# Brd_schematic.net
KiCad netlist of a schematic drawn in Altium Designer
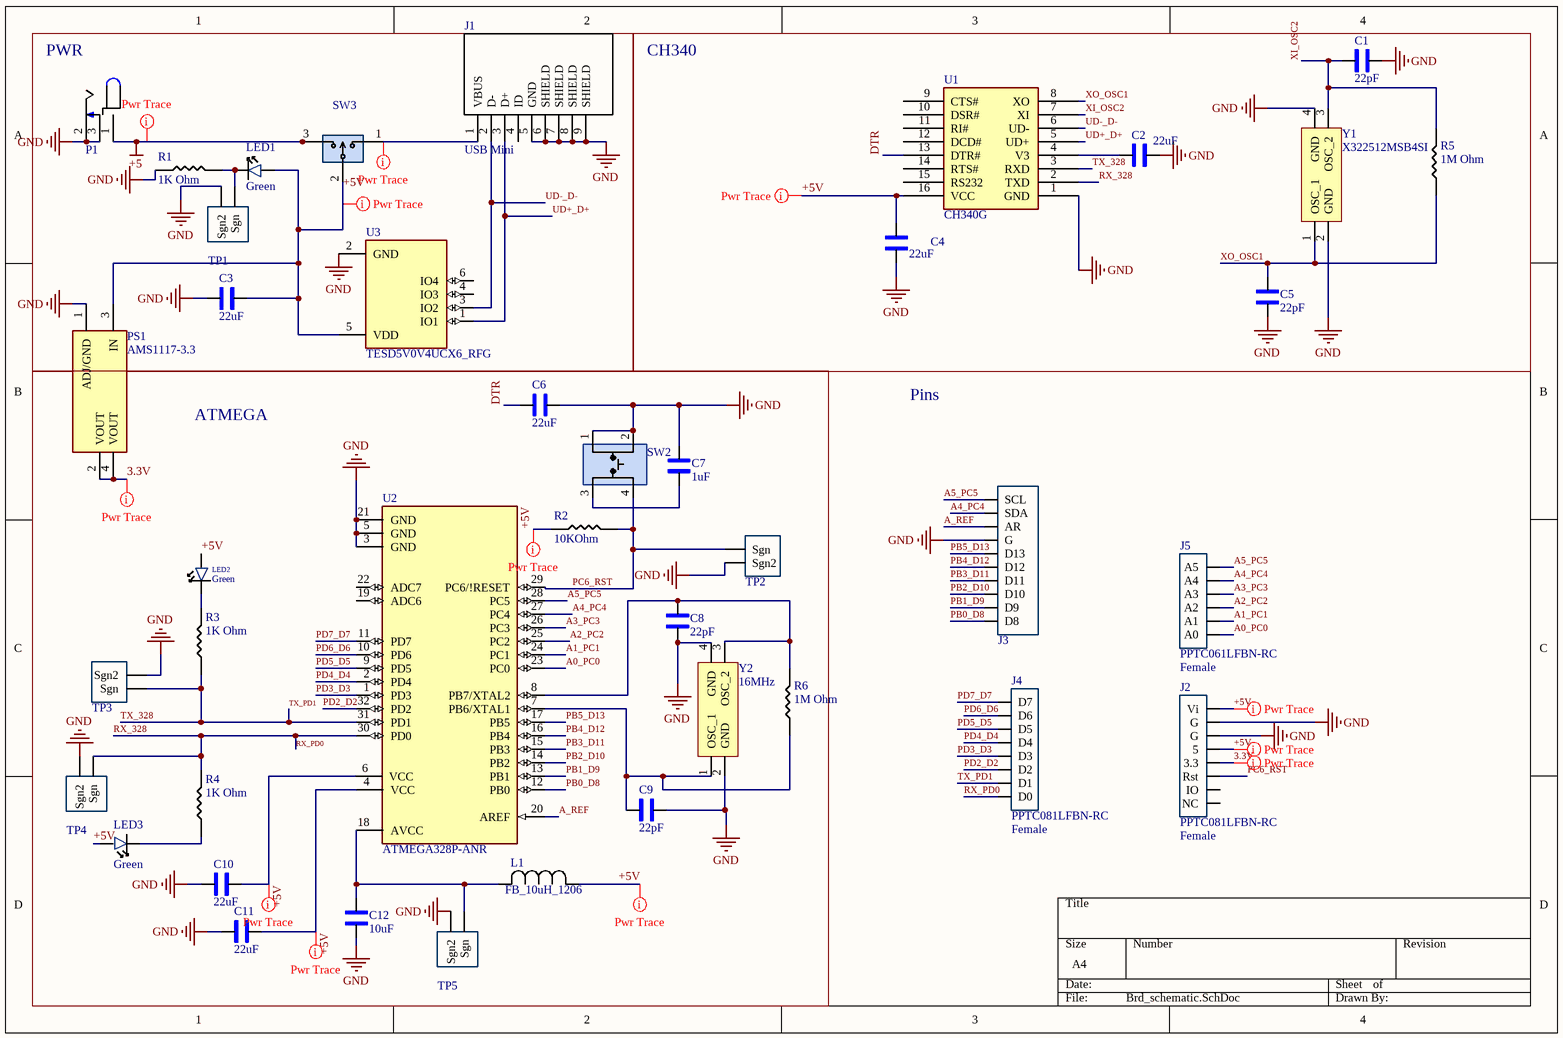
[diagram p0: Brd_schematic.SchDoc]

(export (version "E")
  (design (tool "Eeschema 10.0.6"))
  (components
    (comp (ref "C1")
      (value "22pF")
      (footprint "1206_Passive_Capacitor")
      (description "22pF ±5% 1kV C0G 1206 Multilayer Ceramic Capacitors MLCC - SMD/SMT RoHS")
      (fields (field (name "LCSC PART#") "C107174") (field (name "MFR PART #") "CC1206JKNPOCBN220"))
      (libsource (lib "ECEN5730Lib_2023_05_DS") (part "C_22pF_1206"))
    )
    (comp (ref "C2")
      (value "22uF")
      (footprint "1206_Passive_Capacitor")
      (description "22uF ±10% 25V X5R 1206 Multilayer Ceramic Capacitors MLCC - SMD/SMT RoHS")
      (fields (field (name "MFR PART #") "CL31A226KAHNNNE") (field (name "LCSC PART#") "C12891"))
      (libsource (lib "ECEN5730Lib_2023_05_DS") (part "C_22uF_1206"))
    )
    (comp (ref "C3")
      (value "22uF")
      (footprint "1206_Passive_Capacitor")
      (description "22uF ±10% 25V X5R 1206 Multilayer Ceramic Capacitors MLCC - SMD/SMT RoHS")
      (fields (field (name "MFR PART #") "CL31A226KAHNNNE") (field (name "LCSC PART#") "C12891"))
      (libsource (lib "ECEN5730Lib_2023_05_DS") (part "C_22uF_1206"))
    )
    (comp (ref "C4")
      (value "22uF")
      (footprint "1206_Passive_Capacitor")
      (description "22uF ±10% 25V X5R 1206 Multilayer Ceramic Capacitors MLCC - SMD/SMT RoHS")
      (fields (field (name "MFR PART #") "CL31A226KAHNNNE") (field (name "LCSC PART#") "C12891"))
      (libsource (lib "ECEN5730Lib_2023_05_DS") (part "C_22uF_1206"))
    )
    (comp (ref "C5")
      (value "22pF")
      (footprint "1206_Passive_Capacitor")
      (description "22pF ±5% 1kV C0G 1206 Multilayer Ceramic Capacitors MLCC - SMD/SMT RoHS")
      (fields (field (name "LCSC PART#") "C107174") (field (name "MFR PART #") "CC1206JKNPOCBN220"))
      (libsource (lib "ECEN5730Lib_2023_05_DS") (part "C_22pF_1206"))
    )
    (comp (ref "C6")
      (value "22uF")
      (footprint "1206_Passive_Capacitor")
      (description "22uF ±10% 25V X5R 1206 Multilayer Ceramic Capacitors MLCC - SMD/SMT RoHS")
      (fields (field (name "MFR PART #") "CL31A226KAHNNNE") (field (name "LCSC PART#") "C12891"))
      (libsource (lib "ECEN5730Lib_2023_05_DS") (part "C_22uF_1206"))
    )
    (comp (ref "C7")
      (value "1uF")
      (footprint "1206_Passive_Capacitor")
      (description "MULTILAYER CERAMIC CAPACITORS MLCC - SMD/SMT 1UF 50V 1206 ROHS")
      (fields (field (name "MFR PART #") "CL31B105KBHNNNE") (field (name "LCSC PART#") "C1848"))
      (libsource (lib "ECEN5730Lib_2023_05_DS") (part "C_1uF_1206"))
    )
    (comp (ref "C8")
      (value "22pF")
      (footprint "1206_Passive_Capacitor")
      (description "22pF ±5% 1kV C0G 1206 Multilayer Ceramic Capacitors MLCC - SMD/SMT RoHS")
      (fields (field (name "LCSC PART#") "C107174") (field (name "MFR PART #") "CC1206JKNPOCBN220"))
      (libsource (lib "ECEN5730Lib_2023_05_DS") (part "C_22pF_1206"))
    )
    (comp (ref "C9")
      (value "22pF")
      (footprint "1206_Passive_Capacitor")
      (description "22pF ±5% 1kV C0G 1206 Multilayer Ceramic Capacitors MLCC - SMD/SMT RoHS")
      (fields (field (name "LCSC PART#") "C107174") (field (name "MFR PART #") "CC1206JKNPOCBN220"))
      (libsource (lib "ECEN5730Lib_2023_05_DS") (part "C_22pF_1206"))
    )
    (comp (ref "C10")
      (value "22uF")
      (footprint "1206_Passive_Capacitor")
      (description "22uF ±10% 25V X5R 1206 Multilayer Ceramic Capacitors MLCC - SMD/SMT RoHS")
      (fields (field (name "MFR PART #") "CL31A226KAHNNNE") (field (name "LCSC PART#") "C12891"))
      (libsource (lib "ECEN5730Lib_2023_05_DS") (part "C_22uF_1206"))
    )
    (comp (ref "C11")
      (value "22uF")
      (footprint "1206_Passive_Capacitor")
      (description "22uF ±10% 25V X5R 1206 Multilayer Ceramic Capacitors MLCC - SMD/SMT RoHS")
      (fields (field (name "MFR PART #") "CL31A226KAHNNNE") (field (name "LCSC PART#") "C12891"))
      (libsource (lib "ECEN5730Lib_2023_05_DS") (part "C_22uF_1206"))
    )
    (comp (ref "C12")
      (value "10uF")
      (footprint "1206_Passive_Capacitor")
      (description "10uF ±10% 50V X5R 1206 Multilayer Ceramic Capacitors MLCC - SMD/SMT RoHS")
      (fields (field (name "LCSC PART#") "C13585") (field (name "MFR PART #") "CL31A106KBHNNNE"))
      (libsource (lib "ECEN5730Lib_2023_05_DS") (part "C_10uF_1206"))
    )
    (comp (ref "J1")
      (value "USB Mini")
      (footprint "USB_MINI_B")
      (description "Through Hole USB Connectors RoHS")
      (fields (field (name "LCSC PART#") "C46398") (field (name "MFR PART #") "920-462A2021D10102"))
      (libsource (lib "ECEN5730Lib_2023_05_DS") (part "J_USB_B_Mini"))
    )
    (comp (ref "J2")
      (value "PPTC081LFBN-RC")
      (footprint "8_PIN_ARD-PWR_100MIL")
      (description "8 Position Header Connector 0.100\" (2.54mm) Through Hole Tin")
      (fields (field (name "LCSC PART#") "C27438") (field (name "ALTIUM_VALUE") "Female"))
      (libsource (lib "ECEN5730Lib_2023_05_DS") (part "JF_8_PIN_FEMA_ARD-Pwr"))
    )
    (comp (ref "J3")
      (value "PPTC101LFBN-RC")
      (footprint "10_PIN_ARDUINO_100MIL")
      (description "10 Position Header Connector 0.100\" (2.54mm) Through Hole Tin")
      (fields (field (name "LCSC PART#") "C225507"))
      (libsource (lib "ECEN5730Lib_2023_05_DS") (part "JF_10_PIN_FEMA_ARDUINO"))
    )
    (comp (ref "J4")
      (value "PPTC081LFBN-RC")
      (footprint "8_PIN_ARD-DIG_100MIL")
      (description "8 Position Header Connector 0.100\" (2.54mm) Through Hole Tin")
      (fields (field (name "LCSC PART#") "C27438") (field (name "ALTIUM_VALUE") "Female"))
      (libsource (lib "ECEN5730Lib_2023_05_DS") (part "JF_8_PIN_FEMA_ARD-Dig"))
    )
    (comp (ref "J5")
      (value "PPTC061LFBN-RC")
      (footprint "6_PIN_ARD-Analog_100mil")
      (description "6 Position Header Connector 0.100\" (2.54mm) Through Hole Tin")
      (fields (field (name "LCSC PART#") "C40877") (field (name "ALTIUM_VALUE") "Female"))
      (libsource (lib "ECEN5730Lib_2023_05_DS") (part "JF_6_PIN_FEMA_ARD-Anolog"))
    )
    (comp (ref "L1")
      (value "FB_10uH_1206")
      (footprint "AIML-1206_ABR-M")
      (description "25mA 10uH ±10% 800mΩ 1206  Inductors (SMD) ROHS")
      (fields (field (name "MFR PART #") "CMI321609X100KT") (field (name "LCSC PART#") "C1051"))
      (libsource (lib "ECEN5730Lib_2023_05_DS") (part "FB_10uH_1206"))
    )
    (comp (ref "LED1")
      (value "Green")
      (footprint "LED_1206")
      (description "Green 513~528nm 1206 Light Emitting Diodes (LED) RoHS")
      (fields (field (name "MFR PART #") "SZYY1206G") (field (name "LCSC PART#") "C434439"))
      (libsource (lib "ECEN5730Lib_2023_05_DS") (part "LED_GREEN_1206"))
    )
    (comp (ref "LED2")
      (value "Green")
      (footprint "LED_1206")
      (description "Green 513~528nm 1206 Light Emitting Diodes (LED) RoHS")
      (fields (field (name "MFR PART #") "SZYY1206G") (field (name "LCSC PART#") "C434439"))
      (libsource (lib "ECEN5730Lib_2023_05_DS") (part "LED_GREEN_1206"))
    )
    (comp (ref "LED3")
      (value "Green")
      (footprint "LED_1206")
      (description "Green 513~528nm 1206 Light Emitting Diodes (LED) RoHS")
      (fields (field (name "MFR PART #") "SZYY1206G") (field (name "LCSC PART#") "C434439"))
      (libsource (lib "ECEN5730Lib_2023_05_DS") (part "LED_GREEN_1206"))
    )
    (comp (ref "P1")
      (value "Power Jack")
      (footprint "Power_Jack")
      (description "Power Barrel Connector Jack 2.10mm ID (0.083\"), 5.50mm OD (0.217\") Through Hole, Right Angle")
      (fields (field (name "MFR PART #") "PJ-102A") (field (name "LCSC PART#") "C136744"))
      (libsource (lib "ECEN5730Lib_2023_05_DS") (part "P_Power Jack"))
    )
    (comp (ref "PS1")
      (value "AMS1117-3.3")
      (footprint "LDO")
      (description "LOW DROPOUT REGULATORS(LDO) POSITIVE FIXED 1.3V @ 800MA 15V 3.3V 1A SOT-223 ROHS")
      (fields (field (name "LCSC PART#") "C6186"))
      (libsource (lib "ECEN5730Lib_2023_05_DS") (part "PS_AMS_LDO_3v3"))
    )
    (comp (ref "R1")
      (value "1K Ohm")
      (footprint "1206_Passive_Resitor")
      (description "CHIP RESISTOR - SURFACE MOUNT 1KOHMS ±1% 1/4W 1206 ROHS")
      (fields (field (name "MFR PART #") "RNCP1206FTD1K00CT") (field (name "LCSC PART#") "C4410"))
      (libsource (lib "ECEN5730Lib_2023_05_DS") (part "R_1K_1206"))
    )
    (comp (ref "R2")
      (value "10KOhm")
      (footprint "1206_Passive_Resitor")
      (description "10 kOhms ±5% 0.25W, 1/4W Chip Resistor 1206 (3216 Metric) Automotive AEC-Q200 Thick Film")
      (fields (field (name "MFR PART #") "RMCF1206FT10K0") (field (name "LCSC PART#") "C17902"))
      (libsource (lib "ECEN5730Lib_2023_05_DS") (part "R_10KOhm_1206"))
    )
    (comp (ref "R3")
      (value "1K Ohm")
      (footprint "1206_Passive_Resitor")
      (description "CHIP RESISTOR - SURFACE MOUNT 1KOHMS ±1% 1/4W 1206 ROHS")
      (fields (field (name "MFR PART #") "RNCP1206FTD1K00CT") (field (name "LCSC PART#") "C4410"))
      (libsource (lib "ECEN5730Lib_2023_05_DS") (part "R_1K_1206"))
    )
    (comp (ref "R4")
      (value "1K Ohm")
      (footprint "1206_Passive_Resitor")
      (description "CHIP RESISTOR - SURFACE MOUNT 1KOHMS ±1% 1/4W 1206 ROHS")
      (fields (field (name "MFR PART #") "RNCP1206FTD1K00CT") (field (name "LCSC PART#") "C4410"))
      (libsource (lib "ECEN5730Lib_2023_05_DS") (part "R_1K_1206"))
    )
    (comp (ref "R5")
      (value "1M Ohm")
      (footprint "1206_Passive_Resitor")
      (description "CHIP RESISTOR - SURFACE MOUNT 1MOHMS ±1% 1/4W 1206 ROHS")
      (fields (field (name "MFR PART #") "RMCF1206JT1M00") (field (name "LCSC PART#") "C17927"))
      (libsource (lib "ECEN5730Lib_2023_05_DS") (part "R_1M_1206"))
    )
    (comp (ref "R6")
      (value "1M Ohm")
      (footprint "1206_Passive_Resitor")
      (description "CHIP RESISTOR - SURFACE MOUNT 1MOHMS ±1% 1/4W 1206 ROHS")
      (fields (field (name "MFR PART #") "RMCF1206JT1M00") (field (name "LCSC PART#") "C17927"))
      (libsource (lib "ECEN5730Lib_2023_05_DS") (part "R_1M_1206"))
    )
    (comp (ref "SW2")
      (value "TL3305AF160QG")
      (footprint "Switch_JLC")
      (description "Tactile Switch SPST-NO Top Actuated Surface Mount")
      (fields (field (name "MFR PART #") "KH-4.5X4.5X4.3H-STM") (field (name "LCSC PART#") "C2837550"))
      (libsource (lib "ECEN5730Lib_2023_05_DS") (part "SW_Push_Button_JLC"))
    )
    (comp (ref "SW3")
      (value "PREC003SAAN-RC")
      (footprint "3_PIN_100mil")
      (description "Connector Header Through Hole 3 position 0.100\" (2.54mm)")
      (fields (field (name "LCSC PART#") "C49257"))
      (libsource (lib "ECEN5730Lib_2023_05_DS") (part "SW_3Pin_100mil_Switch"))
    )
    (comp (ref "TP1")
      (value "10x Probe TP")
      (footprint "TP_Diff_Probe")
      (description "Test Point 300 mil centers")
      (libsource (lib "ECEN5730Lib_2023_05_DS") (part "TP_Diff_Probe"))
    )
    (comp (ref "TP2")
      (value "10x Probe TP")
      (footprint "TP_Diff_Probe")
      (description "Test Point 300 mil centers")
      (libsource (lib "") (part "TP_Diff_Probe_1"))
    )
    (comp (ref "TP3")
      (value "10x Probe TP")
      (footprint "TP_Diff_Probe")
      (description "Test Point 300 mil centers")
      (libsource (lib "") (part "TP_Diff_Probe_2"))
    )
    (comp (ref "TP4")
      (value "10x Probe TP")
      (footprint "TP_Diff_Probe")
      (description "Test Point 300 mil centers")
      (libsource (lib "ECEN5730Lib_2023_05_DS") (part "TP_Diff_Probe"))
    )
    (comp (ref "TP5")
      (value "10x Probe TP")
      (footprint "TP_Diff_Probe")
      (description "Test Point 300 mil centers")
      (libsource (lib "ECEN5730Lib_2023_05_DS") (part "TP_Diff_Probe"))
    )
    (comp (ref "U1")
      (value "CH340G")
      (footprint "USB to serial")
      (description "Transceiver USB 2.0 2Mbps SOP-16_150mil USB ICs RoHS")
      (fields (field (name "LCSC PART#") "C14267"))
      (libsource (lib "ECEN5730Lib_2023_05_DS") (part "U_USBtoSerial"))
    )
    (comp (ref "U2")
      (value "ATMEGA328P-ANR")
      (footprint "ATMega328P")
      (description "AVR AVR® ATmega Microcontroller IC 8-Bit 20MHz 32KB (16K x 16) FLASH 32-TQFP (7x7)")
      (fields (field (name "MFR PART #") "ATMEGA328P-AU") (field (name "LCSC PART#") "C14877"))
      (libsource (lib "ECEN5730Lib_2023_05_DS") (part "U_ATMega328P"))
    )
    (comp (ref "U3")
      (value "TESD5V0V4UCX6_RFG")
      (footprint "SOT95P280X145-6N")
      (description "SOT-26, 5V, 75W, 0.6pF, ESD Protection")
      (fields (field (name "MF") "Taiwan Semiconductor") (field (name "MP") "TESD5V0V4UCX6 RFG"))
      (libsource (lib "TESD5V0V4UCX6_RFG") (part "TESD5V0V4UCX6_RFG"))
    )
    (comp (ref "Y1")
      (value "X322512MSB4SI")
      (footprint "Crystal resonator")
      (description "SMD Crystal Resonators 12MHz ±10ppm SMD-3225_4P RoHS")
      (fields (field (name "LCSC PART#") "C9002"))
      (libsource (lib "ECEN5730Lib_2023_05_DS") (part "X_12MHz_Res"))
    )
    (comp (ref "Y2")
      (value "16MHz")
      (footprint "Crystal resonator")
      (description "±10ppm 16000000Hz -40℃~85℃ 贴片无源晶振 60Ω 9pF SMD3225-4P Crystals ROHS")
      (fields (field (name "LCSC PART#") "C13738") (field (name "MFR PART #") "X322516MLB4SI"))
      (libsource (lib "ECEN5730Lib_2023_05_DS") (part "X_16Mhz_Res"))
    )
  )
  (nets
    (net (code "1") (name "+5") (class "Default")
      (node (ref "P1") (pin "1") (pinfunction "1_1") (pintype "power_in"))
      (node (ref "SW3") (pin "3") (pinfunction "3_3") (pintype "passive"))
    )
    (net (code "2") (name "/+5V") (class "Default")
      (node (ref "C10") (pin "2") (pinfunction "2_2") (pintype "passive"))
      (node (ref "C11") (pin "2") (pinfunction "2_2") (pintype "passive"))
      (node (ref "C3") (pin "2") (pinfunction "2_2") (pintype "passive"))
      (node (ref "C4") (pin "2") (pinfunction "2_2") (pintype "passive"))
      (node (ref "J2") (pin "5") (pinfunction "5_5") (pintype "passive"))
      (node (ref "J2") (pin "8") (pinfunction "Vi_8") (pintype "passive"))
      (node (ref "L1") (pin "1") (pinfunction "1_1") (pintype "passive"))
      (node (ref "LED1") (pin "1") (pinfunction "1_1") (pintype "passive"))
      (node (ref "LED2") (pin "1") (pinfunction "1_1") (pintype "passive"))
      (node (ref "LED3") (pin "1") (pinfunction "1_1") (pintype "passive"))
      (node (ref "PS1") (pin "3") (pinfunction "IN_3") (pintype "power_in"))
      (node (ref "R2") (pin "1") (pinfunction "1_1") (pintype "passive"))
      (node (ref "SW3") (pin "2") (pinfunction "2_2") (pintype "passive"))
      (node (ref "U1") (pin "16") (pinfunction "VCC_16") (pintype "passive"))
      (node (ref "U2") (pin "4") (pinfunction "VCC_4") (pintype "power_in"))
      (node (ref "U2") (pin "6") (pinfunction "VCC_6") (pintype "power_in"))
      (node (ref "U3") (pin "5") (pinfunction "VDD_5") (pintype "power_in"))
    )
    (net (code "3") (name "/3.3V") (class "Default")
      (node (ref "J2") (pin "4") (pinfunction "3.3_4") (pintype "passive"))
      (node (ref "PS1") (pin "2") (pinfunction "VOUT_2") (pintype "power_in"))
      (node (ref "PS1") (pin "4") (pinfunction "VOUT_4") (pintype "power_in"))
    )
    (net (code "4") (name "/A0_PC0") (class "Default")
      (node (ref "J5") (pin "1") (pinfunction "A0_1") (pintype "passive"))
      (node (ref "U2") (pin "23") (pinfunction "PC0_23") (pintype "bidirectional"))
    )
    (net (code "5") (name "/A1_PC1") (class "Default")
      (node (ref "J5") (pin "2") (pinfunction "A1_2") (pintype "passive"))
      (node (ref "U2") (pin "24") (pinfunction "PC1_24") (pintype "bidirectional"))
    )
    (net (code "6") (name "/A2_PC2") (class "Default")
      (node (ref "J5") (pin "3") (pinfunction "A2_3") (pintype "passive"))
      (node (ref "U2") (pin "25") (pinfunction "PC2_25") (pintype "bidirectional"))
    )
    (net (code "7") (name "/A3_PC3") (class "Default")
      (node (ref "J5") (pin "4") (pinfunction "A3_4") (pintype "passive"))
      (node (ref "U2") (pin "26") (pinfunction "PC3_26") (pintype "bidirectional"))
    )
    (net (code "8") (name "/A4_PC4") (class "Default")
      (node (ref "J3") (pin "2") (pinfunction "SDA_2") (pintype "passive"))
      (node (ref "J5") (pin "5") (pinfunction "A4_5") (pintype "passive"))
      (node (ref "U2") (pin "27") (pinfunction "PC4_27") (pintype "bidirectional"))
    )
    (net (code "9") (name "/A5_PC5") (class "Default")
      (node (ref "J3") (pin "1") (pinfunction "SCL_1") (pintype "passive"))
      (node (ref "J5") (pin "6") (pinfunction "A5_6") (pintype "passive"))
      (node (ref "U2") (pin "28") (pinfunction "PC5_28") (pintype "bidirectional"))
    )
    (net (code "10") (name "/A_REF") (class "Default")
      (node (ref "J3") (pin "3") (pinfunction "AR_3") (pintype "passive"))
      (node (ref "U2") (pin "20") (pinfunction "AREF_20") (pintype "input"))
    )
    (net (code "11") (name "/DTR") (class "Default")
      (node (ref "C6") (pin "1") (pinfunction "1_1") (pintype "passive"))
      (node (ref "U1") (pin "13") (pinfunction "DTR#_13") (pintype "passive"))
    )
    (net (code "12") (name "/PB0_D8") (class "Default")
      (node (ref "J3") (pin "10") (pinfunction "D8_10") (pintype "passive"))
      (node (ref "U2") (pin "12") (pinfunction "PB0_12") (pintype "bidirectional"))
    )
    (net (code "13") (name "/PB1_D9") (class "Default")
      (node (ref "J3") (pin "9") (pinfunction "D9_9") (pintype "passive"))
      (node (ref "U2") (pin "13") (pinfunction "PB1_13") (pintype "bidirectional"))
    )
    (net (code "14") (name "/PB2_D10") (class "Default")
      (node (ref "J3") (pin "8") (pinfunction "D10_8") (pintype "passive"))
      (node (ref "U2") (pin "14") (pinfunction "PB2_14") (pintype "bidirectional"))
    )
    (net (code "15") (name "/PB3_D11") (class "Default")
      (node (ref "J3") (pin "7") (pinfunction "D11_7") (pintype "passive"))
      (node (ref "U2") (pin "15") (pinfunction "PB3_15") (pintype "bidirectional"))
    )
    (net (code "16") (name "/PB4_D12") (class "Default")
      (node (ref "J3") (pin "6") (pinfunction "D12_6") (pintype "passive"))
      (node (ref "U2") (pin "16") (pinfunction "PB4_16") (pintype "bidirectional"))
    )
    (net (code "17") (name "/PB5_D13") (class "Default")
      (node (ref "J3") (pin "5") (pinfunction "D13_5") (pintype "passive"))
      (node (ref "U2") (pin "17") (pinfunction "PB5_17") (pintype "bidirectional"))
    )
    (net (code "18") (name "/PC6_RST") (class "Default")
      (node (ref "J2") (pin "3") (pinfunction "Rst_3") (pintype "passive"))
      (node (ref "R2") (pin "2") (pinfunction "2_2") (pintype "passive"))
      (node (ref "SW2") (pin "4") (pinfunction "4_4") (pintype "passive"))
      (node (ref "TP2") (pin "1") (pinfunction "Sgn_1") (pintype "passive"))
      (node (ref "U2") (pin "29") (pinfunction "PC6/!RESET_29") (pintype "bidirectional"))
    )
    (net (code "19") (name "/PD2_D2") (class "Default")
      (node (ref "J4") (pin "6") (pinfunction "D2_6") (pintype "passive"))
      (node (ref "U2") (pin "32") (pinfunction "PD2_32") (pintype "bidirectional"))
    )
    (net (code "20") (name "/PD3_D3") (class "Default")
      (node (ref "J4") (pin "5") (pinfunction "D3_5") (pintype "passive"))
      (node (ref "U2") (pin "1") (pinfunction "PD3_1") (pintype "bidirectional"))
    )
    (net (code "21") (name "/PD4_D4") (class "Default")
      (node (ref "J4") (pin "4") (pinfunction "D4_4") (pintype "passive"))
      (node (ref "U2") (pin "2") (pinfunction "PD4_2") (pintype "bidirectional"))
    )
    (net (code "22") (name "/PD5_D5") (class "Default")
      (node (ref "J4") (pin "3") (pinfunction "D5_3") (pintype "passive"))
      (node (ref "U2") (pin "9") (pinfunction "PD5_9") (pintype "bidirectional"))
    )
    (net (code "23") (name "/PD6_D6") (class "Default")
      (node (ref "J4") (pin "2") (pinfunction "D6_2") (pintype "passive"))
      (node (ref "U2") (pin "10") (pinfunction "PD6_10") (pintype "bidirectional"))
    )
    (net (code "24") (name "/PD7_D7") (class "Default")
      (node (ref "J4") (pin "1") (pinfunction "D7_1") (pintype "passive"))
      (node (ref "U2") (pin "11") (pinfunction "PD7_11") (pintype "bidirectional"))
    )
    (net (code "25") (name "/RX_328") (class "Default")
      (node (ref "J4") (pin "8") (pinfunction "D0_8") (pintype "passive"))
      (node (ref "R4") (pin "2") (pinfunction "2_2") (pintype "passive"))
      (node (ref "TP4") (pin "1") (pinfunction "Sgn_1") (pintype "passive"))
      (node (ref "U1") (pin "2") (pinfunction "TXD_2") (pintype "passive"))
      (node (ref "U2") (pin "30") (pinfunction "PD0_30") (pintype "bidirectional"))
    )
    (net (code "26") (name "/TX_328") (class "Default")
      (node (ref "J4") (pin "7") (pinfunction "D1_7") (pintype "passive"))
      (node (ref "R3") (pin "1") (pinfunction "1_1") (pintype "passive"))
      (node (ref "TP3") (pin "1") (pinfunction "Sgn_1") (pintype "passive"))
      (node (ref "U1") (pin "3") (pinfunction "RXD_3") (pintype "passive"))
      (node (ref "U2") (pin "31") (pinfunction "PD1_31") (pintype "bidirectional"))
    )
    (net (code "27") (name "/UD+_D+") (class "Default")
      (node (ref "J1") (pin "3") (pinfunction "D+_3") (pintype "passive"))
      (node (ref "U1") (pin "5") (pinfunction "UD+_5") (pintype "passive"))
      (node (ref "U3") (pin "1") (pinfunction "IO1_1") (pintype "bidirectional"))
    )
    (net (code "28") (name "/UD-_D-") (class "Default")
      (node (ref "J1") (pin "2") (pinfunction "D-_2") (pintype "passive"))
      (node (ref "U1") (pin "6") (pinfunction "UD-_6") (pintype "passive"))
      (node (ref "U3") (pin "3") (pinfunction "IO2_3") (pintype "bidirectional"))
    )
    (net (code "29") (name "/XI_OSC2") (class "Default")
      (node (ref "C1") (pin "2") (pinfunction "2_2") (pintype "passive"))
      (node (ref "R5") (pin "2") (pinfunction "2_2") (pintype "passive"))
      (node (ref "U1") (pin "7") (pinfunction "XI_7") (pintype "passive"))
      (node (ref "Y1") (pin "3") (pinfunction "OSC_2_3") (pintype "passive"))
    )
    (net (code "30") (name "/XO_OSC1") (class "Default")
      (node (ref "C5") (pin "1") (pinfunction "1_1") (pintype "passive"))
      (node (ref "R5") (pin "1") (pinfunction "1_1") (pintype "passive"))
      (node (ref "U1") (pin "8") (pinfunction "XO_8") (pintype "passive"))
      (node (ref "Y1") (pin "1") (pinfunction "OSC_1_1") (pintype "passive"))
    )
    (net (code "31") (name "GND") (class "Default")
      (node (ref "C1") (pin "1") (pinfunction "1_1") (pintype "passive"))
      (node (ref "C10") (pin "1") (pinfunction "1_1") (pintype "passive"))
      (node (ref "C11") (pin "1") (pinfunction "1_1") (pintype "passive"))
      (node (ref "C12") (pin "1") (pinfunction "1_1") (pintype "passive"))
      (node (ref "C2") (pin "1") (pinfunction "1_1") (pintype "passive"))
      (node (ref "C3") (pin "1") (pinfunction "1_1") (pintype "passive"))
      (node (ref "C4") (pin "1") (pinfunction "1_1") (pintype "passive"))
      (node (ref "C5") (pin "2") (pinfunction "2_2") (pintype "passive"))
      (node (ref "C6") (pin "2") (pinfunction "2_2") (pintype "passive"))
      (node (ref "C7") (pin "2") (pinfunction "2_2") (pintype "passive"))
      (node (ref "C8") (pin "1") (pinfunction "1_1") (pintype "passive"))
      (node (ref "C9") (pin "1") (pinfunction "1_1") (pintype "passive"))
      (node (ref "J1") (pin "5") (pinfunction "GND_5") (pintype "passive"))
      (node (ref "J1") (pin "6") (pinfunction "SHIELD_6") (pintype "passive"))
      (node (ref "J1") (pin "7") (pinfunction "SHIELD_7") (pintype "passive"))
      (node (ref "J1") (pin "8") (pinfunction "SHIELD_8") (pintype "passive"))
      (node (ref "J1") (pin "9") (pinfunction "SHIELD_9") (pintype "passive"))
      (node (ref "J2") (pin "6") (pinfunction "G_6") (pintype "passive"))
      (node (ref "J2") (pin "7") (pinfunction "G_7") (pintype "passive"))
      (node (ref "J3") (pin "4") (pinfunction "G_4") (pintype "passive"))
      (node (ref "P1") (pin "2") (pinfunction "2_2") (pintype "power_in"))
      (node (ref "P1") (pin "3") (pinfunction "3_3") (pintype "power_in"))
      (node (ref "PS1") (pin "1") (pinfunction "ADJ/GND_1") (pintype "passive"))
      (node (ref "R1") (pin "1") (pinfunction "1_1") (pintype "passive"))
      (node (ref "SW2") (pin "1") (pinfunction "1_1") (pintype "passive"))
      (node (ref "SW2") (pin "2") (pinfunction "2_2") (pintype "passive"))
      (node (ref "TP1") (pin "2") (pinfunction "Sgn2_2") (pintype "passive"))
      (node (ref "TP2") (pin "2") (pinfunction "Sgn2_2") (pintype "passive"))
      (node (ref "TP3") (pin "2") (pinfunction "Sgn2_2") (pintype "passive"))
      (node (ref "TP4") (pin "2") (pinfunction "Sgn2_2") (pintype "passive"))
      (node (ref "TP5") (pin "2") (pinfunction "Sgn2_2") (pintype "passive"))
      (node (ref "U1") (pin "1") (pinfunction "GND_1") (pintype "passive"))
      (node (ref "U2") (pin "21") (pinfunction "GND_21") (pintype "power_in"))
      (node (ref "U2") (pin "3") (pinfunction "GND_3") (pintype "power_in"))
      (node (ref "U2") (pin "5") (pinfunction "GND_5") (pintype "power_in"))
      (node (ref "U3") (pin "2") (pinfunction "GND_2") (pintype "power_in"))
      (node (ref "Y1") (pin "2") (pinfunction "GND_2") (pintype "passive"))
      (node (ref "Y1") (pin "4") (pinfunction "GND_4") (pintype "passive"))
      (node (ref "Y2") (pin "2") (pinfunction "GND_2") (pintype "passive"))
      (node (ref "Y2") (pin "4") (pinfunction "GND_4") (pintype "passive"))
    )
    (net (code "32") (name "Net-(C7-Pad1)") (class "Default")
      (node (ref "C7") (pin "1") (pinfunction "1_1") (pintype "passive"))
      (node (ref "SW2") (pin "3") (pinfunction "3_3") (pintype "passive"))
    )
    (net (code "33") (name "Net-(J1-VBUS)") (class "Default")
      (node (ref "J1") (pin "1") (pinfunction "VBUS_1") (pintype "passive"))
      (node (ref "SW3") (pin "1") (pinfunction "1_1") (pintype "passive"))
    )
    (net (code "34") (name "Net-(LED2-Pad2)") (class "Default")
      (node (ref "LED2") (pin "2") (pinfunction "2_2") (pintype "passive"))
      (node (ref "R3") (pin "2") (pinfunction "2_2") (pintype "passive"))
    )
    (net (code "35") (name "Net-(LED3-Pad2)") (class "Default")
      (node (ref "LED3") (pin "2") (pinfunction "2_2") (pintype "passive"))
      (node (ref "R4") (pin "1") (pinfunction "1_1") (pintype "passive"))
    )
    (net (code "36") (name "Net-(TP1-Sgn)") (class "Default")
      (node (ref "LED1") (pin "2") (pinfunction "2_2") (pintype "passive"))
      (node (ref "R1") (pin "2") (pinfunction "2_2") (pintype "passive"))
      (node (ref "TP1") (pin "1") (pinfunction "Sgn_1") (pintype "passive"))
    )
    (net (code "37") (name "Net-(TP5-Sgn)") (class "Default")
      (node (ref "C12") (pin "2") (pinfunction "2_2") (pintype "passive"))
      (node (ref "L1") (pin "2") (pinfunction "2_2") (pintype "passive"))
      (node (ref "TP5") (pin "1") (pinfunction "Sgn_1") (pintype "passive"))
      (node (ref "U2") (pin "18") (pinfunction "AVCC_18") (pintype "power_in"))
    )
    (net (code "38") (name "Net-(U1-V3)") (class "Default")
      (node (ref "C2") (pin "2") (pinfunction "2_2") (pintype "passive"))
      (node (ref "U1") (pin "4") (pinfunction "V3_4") (pintype "passive"))
    )
    (net (code "39") (name "Net-(U2-PB6{slash}XTAL1)") (class "Default")
      (node (ref "C9") (pin "2") (pinfunction "2_2") (pintype "passive"))
      (node (ref "R6") (pin "1") (pinfunction "1_1") (pintype "passive"))
      (node (ref "U2") (pin "7") (pinfunction "PB6/XTAL1_7") (pintype "bidirectional"))
      (node (ref "Y2") (pin "1") (pinfunction "OSC_1_1") (pintype "passive"))
    )
    (net (code "40") (name "Net-(U2-PB7{slash}XTAL2)") (class "Default")
      (node (ref "C8") (pin "2") (pinfunction "2_2") (pintype "passive"))
      (node (ref "R6") (pin "2") (pinfunction "2_2") (pintype "passive"))
      (node (ref "U2") (pin "8") (pinfunction "PB7/XTAL2_8") (pintype "bidirectional"))
      (node (ref "Y2") (pin "3") (pinfunction "OSC_2_3") (pintype "passive"))
    )
    (net (code "41") (name "unconnected-(J1-ID-Pad4)") (class "Default")
      (node (ref "J1") (pin "4") (pinfunction "ID_4") (pintype "passive"))
    )
    (net (code "42") (name "unconnected-(J2-IO-Pad2)") (class "Default")
      (node (ref "J2") (pin "2") (pinfunction "IO_2") (pintype "passive"))
    )
    (net (code "43") (name "unconnected-(J2-NC-Pad1)") (class "Default")
      (node (ref "J2") (pin "1") (pinfunction "NC_1") (pintype "passive"))
    )
    (net (code "44") (name "unconnected-(U1-CTS#-Pad9)") (class "Default")
      (node (ref "U1") (pin "9") (pinfunction "CTS#_9") (pintype "passive"))
    )
    (net (code "45") (name "unconnected-(U1-DCD#-Pad12)") (class "Default")
      (node (ref "U1") (pin "12") (pinfunction "DCD#_12") (pintype "passive"))
    )
    (net (code "46") (name "unconnected-(U1-DSR#-Pad10)") (class "Default")
      (node (ref "U1") (pin "10") (pinfunction "DSR#_10") (pintype "passive"))
    )
    (net (code "47") (name "unconnected-(U1-RI#-Pad11)") (class "Default")
      (node (ref "U1") (pin "11") (pinfunction "RI#_11") (pintype "passive"))
    )
    (net (code "48") (name "unconnected-(U1-RS232-Pad15)") (class "Default")
      (node (ref "U1") (pin "15") (pinfunction "RS232_15") (pintype "passive"))
    )
    (net (code "49") (name "unconnected-(U1-RTS#-Pad14)") (class "Default")
      (node (ref "U1") (pin "14") (pinfunction "RTS#_14") (pintype "passive"))
    )
    (net (code "50") (name "unconnected-(U2-ADC6-Pad19)") (class "Default")
      (node (ref "U2") (pin "19") (pinfunction "ADC6_19") (pintype "bidirectional"))
    )
    (net (code "51") (name "unconnected-(U2-ADC7-Pad22)") (class "Default")
      (node (ref "U2") (pin "22") (pinfunction "ADC7_22") (pintype "bidirectional"))
    )
    (net (code "52") (name "unconnected-(U3-IO3-Pad4)") (class "Default")
      (node (ref "U3") (pin "4") (pinfunction "IO3_4") (pintype "bidirectional"))
    )
    (net (code "53") (name "unconnected-(U3-IO4-Pad6)") (class "Default")
      (node (ref "U3") (pin "6") (pinfunction "IO4_6") (pintype "bidirectional"))
    )
  )
)
